# AudioMega_v101.net
KiCad netlist of a schematic drawn in EAGLE
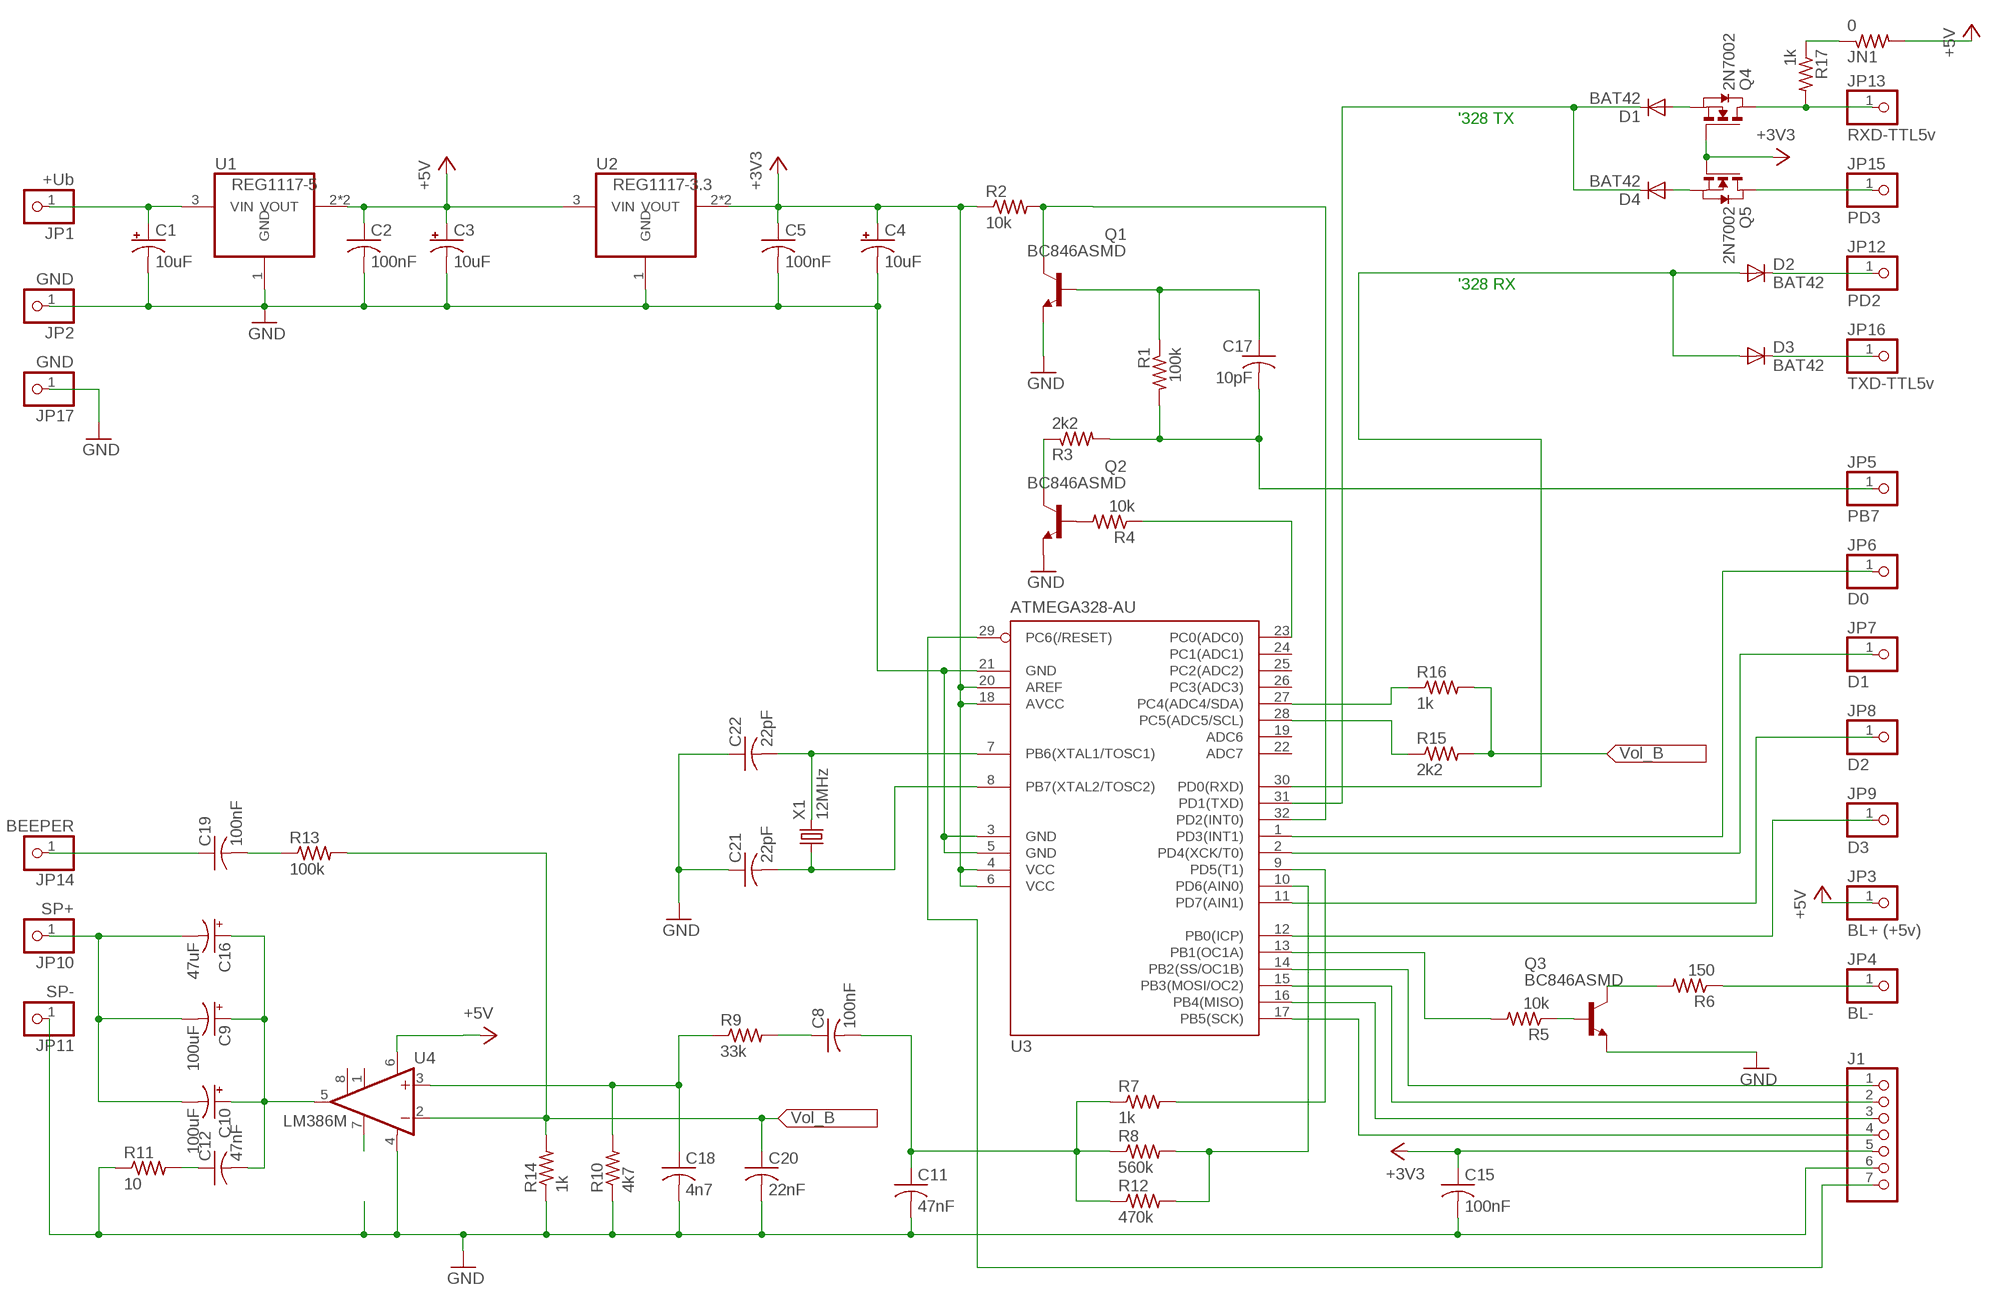
[diagram p0: schematic, sheet 1]

(export (version "E")
  (design (tool "Eeschema 10.0.6"))
  (components
    (comp (ref "C1")
      (value "10uF")
      (footprint "eagle-import:CT3528")
      (libsource (lib "eagle-import") (part "CPOL-USCT3528"))
    )
    (comp (ref "C2")
      (value "100nF")
      (footprint "eagle-import:C1206")
      (libsource (lib "eagle-import") (part "C-USC1206"))
    )
    (comp (ref "C3")
      (value "10uF")
      (footprint "eagle-import:CT3528")
      (libsource (lib "eagle-import") (part "CPOL-USCT3528"))
    )
    (comp (ref "C4")
      (value "10uF")
      (footprint "eagle-import:CT3528")
      (libsource (lib "eagle-import") (part "CPOL-USCT3528"))
    )
    (comp (ref "C5")
      (value "100nF")
      (footprint "eagle-import:C1206")
      (libsource (lib "eagle-import") (part "C-USC1206"))
    )
    (comp (ref "C8")
      (value "100nF")
      (footprint "eagle-import:C1206")
      (libsource (lib "eagle-import") (part "C-USC1206"))
    )
    (comp (ref "C9")
      (value "100uF")
      (footprint "eagle-import:CT6032")
      (libsource (lib "eagle-import") (part "CPOL-USCT6032"))
    )
    (comp (ref "C10")
      (value "100uF")
      (footprint "eagle-import:CT6032")
      (libsource (lib "eagle-import") (part "CPOL-USCT6032"))
    )
    (comp (ref "C11")
      (value "47nF")
      (footprint "eagle-import:C1206")
      (libsource (lib "eagle-import") (part "C-USC1206"))
    )
    (comp (ref "C12")
      (value "47nF")
      (footprint "eagle-import:C1206")
      (libsource (lib "eagle-import") (part "C-USC1206"))
    )
    (comp (ref "C15")
      (value "100nF")
      (footprint "eagle-import:C1206")
      (libsource (lib "eagle-import") (part "C-USC1206"))
    )
    (comp (ref "C16")
      (value "47uF")
      (footprint "eagle-import:CT6032")
      (libsource (lib "eagle-import") (part "CPOL-USCT6032"))
    )
    (comp (ref "C17")
      (value "10pF")
      (footprint "eagle-import:C1206")
      (libsource (lib "eagle-import") (part "C-USC1206"))
    )
    (comp (ref "C18")
      (value "4n7")
      (footprint "eagle-import:C1206")
      (libsource (lib "eagle-import") (part "C-USC1206"))
    )
    (comp (ref "C19")
      (value "100nF")
      (footprint "eagle-import:C1206")
      (libsource (lib "eagle-import") (part "C-USC1206"))
    )
    (comp (ref "C20")
      (value "22nF")
      (footprint "eagle-import:C1206")
      (libsource (lib "eagle-import") (part "C-USC1206"))
    )
    (comp (ref "C21")
      (value "22pF")
      (footprint "eagle-import:C1206")
      (libsource (lib "eagle-import") (part "C-USC1206"))
    )
    (comp (ref "C22")
      (value "22pF")
      (footprint "eagle-import:C1206")
      (libsource (lib "eagle-import") (part "C-USC1206"))
    )
    (comp (ref "D1")
      (value "BAT42")
      (footprint "eagle-import:SOD123")
      (libsource (lib "eagle-import") (part "DIODE-SOD123"))
    )
    (comp (ref "D2")
      (value "BAT42")
      (footprint "eagle-import:SOD123")
      (libsource (lib "eagle-import") (part "DIODE-SOD123"))
    )
    (comp (ref "D3")
      (value "BAT42")
      (footprint "eagle-import:SOD123")
      (libsource (lib "eagle-import") (part "DIODE-SOD123"))
    )
    (comp (ref "D4")
      (value "BAT42")
      (footprint "eagle-import:SOD123")
      (libsource (lib "eagle-import") (part "DIODE-SOD123"))
    )
    (comp (ref "J1")
      (value "PINHD-1X7")
      (footprint "eagle-import:1X07")
      (libsource (lib "eagle-import") (part "PINHD-1X7"))
    )
    (comp (ref "JN1")
      (value "0")
      (footprint "eagle-import:R1206")
      (libsource (lib "eagle-import") (part "R-US_R1206"))
    )
    (comp (ref "JP1")
      (value "+Ub")
      (footprint "eagle-import:1X01")
      (libsource (lib "eagle-import") (part "PINHD-1X1"))
    )
    (comp (ref "JP2")
      (value "GND")
      (footprint "eagle-import:1X01")
      (libsource (lib "eagle-import") (part "PINHD-1X1"))
    )
    (comp (ref "JP3")
      (value "BL+ (+5v)")
      (footprint "eagle-import:1X01")
      (libsource (lib "eagle-import") (part "PINHD-1X1"))
    )
    (comp (ref "JP4")
      (value "BL-")
      (footprint "eagle-import:1X01")
      (libsource (lib "eagle-import") (part "PINHD-1X1"))
    )
    (comp (ref "JP5")
      (value "PB7")
      (footprint "eagle-import:1X01")
      (libsource (lib "eagle-import") (part "PINHD-1X1"))
    )
    (comp (ref "JP6")
      (value "D0")
      (footprint "eagle-import:1X01")
      (libsource (lib "eagle-import") (part "PINHD-1X1"))
    )
    (comp (ref "JP7")
      (value "D1")
      (footprint "eagle-import:1X01")
      (libsource (lib "eagle-import") (part "PINHD-1X1"))
    )
    (comp (ref "JP8")
      (value "D2")
      (footprint "eagle-import:1X01")
      (libsource (lib "eagle-import") (part "PINHD-1X1"))
    )
    (comp (ref "JP9")
      (value "D3")
      (footprint "eagle-import:1X01")
      (libsource (lib "eagle-import") (part "PINHD-1X1"))
    )
    (comp (ref "JP10")
      (value "SP+")
      (footprint "eagle-import:1X01")
      (libsource (lib "eagle-import") (part "PINHD-1X1"))
    )
    (comp (ref "JP11")
      (value "SP-")
      (footprint "eagle-import:1X01")
      (libsource (lib "eagle-import") (part "PINHD-1X1"))
    )
    (comp (ref "JP12")
      (value "PD2")
      (footprint "eagle-import:1X01")
      (libsource (lib "eagle-import") (part "PINHD-1X1"))
    )
    (comp (ref "JP13")
      (value "RXD-TTL5v")
      (footprint "eagle-import:1X01")
      (libsource (lib "eagle-import") (part "PINHD-1X1"))
    )
    (comp (ref "JP14")
      (value "BEEPER")
      (footprint "eagle-import:1X01")
      (libsource (lib "eagle-import") (part "PINHD-1X1"))
    )
    (comp (ref "JP15")
      (value "PD3")
      (footprint "eagle-import:1X01")
      (libsource (lib "eagle-import") (part "PINHD-1X1"))
    )
    (comp (ref "JP16")
      (value "TXD-TTL5v")
      (footprint "eagle-import:1X01")
      (libsource (lib "eagle-import") (part "PINHD-1X1"))
    )
    (comp (ref "JP17")
      (value "GND")
      (footprint "eagle-import:1X01")
      (libsource (lib "eagle-import") (part "PINHD-1X1"))
    )
    (comp (ref "Q1")
      (value "BC846ASMD")
      (footprint "eagle-import:SOT23")
      (libsource (lib "eagle-import") (part "BC846SMDA"))
    )
    (comp (ref "Q2")
      (value "BC846ASMD")
      (footprint "eagle-import:SOT23")
      (libsource (lib "eagle-import") (part "BC846SMDA"))
    )
    (comp (ref "Q3")
      (value "BC846ASMD")
      (footprint "eagle-import:SOT23")
      (libsource (lib "eagle-import") (part "BC846SMDA"))
    )
    (comp (ref "Q4")
      (value "2N7002")
      (footprint "eagle-import:SOT-23")
      (libsource (lib "eagle-import") (part "NMOSSOT23"))
    )
    (comp (ref "Q5")
      (value "2N7002")
      (footprint "eagle-import:SOT-23")
      (fields (field (name "OC_FARNELL") "unknown") (field (name "OC_NEWARK") "unknown"))
      (libsource (lib "eagle-import") (part "NMOSSOT23"))
    )
    (comp (ref "R1")
      (value "100k")
      (footprint "eagle-import:R1206")
      (libsource (lib "eagle-import") (part "R-US_R1206"))
    )
    (comp (ref "R2")
      (value "10k")
      (footprint "eagle-import:R1206")
      (libsource (lib "eagle-import") (part "R-US_R1206"))
    )
    (comp (ref "R3")
      (value "2k2")
      (footprint "eagle-import:R1206")
      (libsource (lib "eagle-import") (part "R-US_R1206"))
    )
    (comp (ref "R4")
      (value "10k")
      (footprint "eagle-import:R1206")
      (libsource (lib "eagle-import") (part "R-US_R1206"))
    )
    (comp (ref "R5")
      (value "10k")
      (footprint "eagle-import:R1206")
      (libsource (lib "eagle-import") (part "R-US_R1206"))
    )
    (comp (ref "R6")
      (value "150")
      (footprint "eagle-import:R1206")
      (libsource (lib "eagle-import") (part "R-US_R1206"))
    )
    (comp (ref "R7")
      (value "1k")
      (footprint "eagle-import:R1206")
      (libsource (lib "eagle-import") (part "R-US_R1206"))
    )
    (comp (ref "R8")
      (value "560k")
      (footprint "eagle-import:R1206")
      (libsource (lib "eagle-import") (part "R-US_R1206"))
    )
    (comp (ref "R9")
      (value "33k")
      (footprint "eagle-import:R1206")
      (libsource (lib "eagle-import") (part "R-US_R1206"))
    )
    (comp (ref "R10")
      (value "4k7")
      (footprint "eagle-import:R1206")
      (libsource (lib "eagle-import") (part "R-US_R1206"))
    )
    (comp (ref "R11")
      (value "10")
      (footprint "eagle-import:R1206")
      (libsource (lib "eagle-import") (part "R-US_R1206"))
    )
    (comp (ref "R12")
      (value "470k")
      (footprint "eagle-import:R1206")
      (libsource (lib "eagle-import") (part "R-US_R1206"))
    )
    (comp (ref "R13")
      (value "100k")
      (footprint "eagle-import:R1206")
      (libsource (lib "eagle-import") (part "R-US_R1206"))
    )
    (comp (ref "R14")
      (value "1k")
      (footprint "eagle-import:R1206")
      (libsource (lib "eagle-import") (part "R-US_R1206"))
    )
    (comp (ref "R15")
      (value "2k2")
      (footprint "eagle-import:R1206")
      (libsource (lib "eagle-import") (part "R-US_R1206"))
    )
    (comp (ref "R16")
      (value "1k")
      (footprint "eagle-import:R1206")
      (libsource (lib "eagle-import") (part "R-US_R1206"))
    )
    (comp (ref "R17")
      (value "1k")
      (footprint "eagle-import:R1206")
      (libsource (lib "eagle-import") (part "R-US_R1206"))
    )
    (comp (ref "U1")
      (value "REG1117-5")
      (footprint "eagle-import:SOT223")
      (fields (field (name "MPN") "REG1117"))
      (libsource (lib "eagle-import") (part "REG1117"))
    )
    (comp (ref "U2")
      (value "REG1117-3.3")
      (footprint "eagle-import:SOT223")
      (fields (field (name "MPN") "REG1117"))
      (libsource (lib "eagle-import") (part "REG1117"))
    )
    (comp (ref "U3")
      (value "ATMEGA328-AU")
      (footprint "eagle-import:TQFP32-08")
      (fields (field (name "MPN") "ATMEGA8-16AU"))
      (libsource (lib "eagle-import") (part "MEGA8-AI"))
    )
    (comp (ref "U4")
      (value "LM386M")
      (footprint "eagle-import:SO08")
      (libsource (lib "eagle-import") (part "LM386?-M1"))
    )
    (comp (ref "X1")
      (value "12MHz")
      (footprint "eagle-import:HC49UP")
      (libsource (lib "eagle-import") (part "CRYSTALHC49UP"))
    )
  )
  (nets
    (net (code "1") (name "+3V3") (class "Default")
      (node (ref "C15") (pin "1") (pinfunction "1_1") (pintype "passive"))
      (node (ref "C4") (pin "+") (pinfunction "+_+") (pintype "passive"))
      (node (ref "C5") (pin "1") (pinfunction "1_1") (pintype "passive"))
      (node (ref "J1") (pin "5") (pinfunction "5_5") (pintype "passive"))
      (node (ref "Q4") (pin "3") (pinfunction "G_3") (pintype "passive"))
      (node (ref "Q5") (pin "3") (pinfunction "G_3") (pintype "passive"))
      (node (ref "R2") (pin "1") (pinfunction "1_1") (pintype "passive"))
      (node (ref "U2") (pin "2") (pinfunction "VOUT_2") (pintype "output"))
      (node (ref "U2") (pin "4") (pinfunction "VOUT_4") (pintype "output"))
      (node (ref "U3") (pin "18") (pinfunction "AVCC_18") (pintype "power_in"))
      (node (ref "U3") (pin "20") (pinfunction "AREF_20") (pintype "passive"))
      (node (ref "U3") (pin "4") (pinfunction "VCC_4") (pintype "power_in"))
      (node (ref "U3") (pin "6") (pinfunction "VCC_6") (pintype "power_in"))
    )
    (net (code "2") (name "+5V") (class "Default")
      (node (ref "C2") (pin "1") (pinfunction "1_1") (pintype "passive"))
      (node (ref "C3") (pin "+") (pinfunction "+_+") (pintype "passive"))
      (node (ref "JN1") (pin "2") (pinfunction "2_2") (pintype "passive"))
      (node (ref "JP3") (pin "1") (pinfunction "1_1") (pintype "passive"))
      (node (ref "U1") (pin "2") (pinfunction "VOUT_2") (pintype "output"))
      (node (ref "U1") (pin "4") (pinfunction "VOUT_4") (pintype "output"))
      (node (ref "U2") (pin "3") (pinfunction "VIN_3") (pintype "input"))
      (node (ref "U4") (pin "6") (pinfunction "VS_6") (pintype "power_in"))
    )
    (net (code "3") (name "/VOL_B") (class "Default")
      (node (ref "C20") (pin "1") (pinfunction "1_1") (pintype "passive"))
      (node (ref "R13") (pin "2") (pinfunction "2_2") (pintype "passive"))
      (node (ref "R14") (pin "2") (pinfunction "2_2") (pintype "passive"))
      (node (ref "R15") (pin "2") (pinfunction "2_2") (pintype "passive"))
      (node (ref "R16") (pin "2") (pinfunction "2_2") (pintype "passive"))
      (node (ref "U4") (pin "2") (pinfunction "-IN_2") (pintype "input"))
    )
    (net (code "4") (name "GND") (class "Default")
      (node (ref "C1") (pin "-") (pinfunction "-_-") (pintype "passive"))
      (node (ref "C11") (pin "2") (pinfunction "2_2") (pintype "passive"))
      (node (ref "C15") (pin "2") (pinfunction "2_2") (pintype "passive"))
      (node (ref "C18") (pin "2") (pinfunction "2_2") (pintype "passive"))
      (node (ref "C2") (pin "2") (pinfunction "2_2") (pintype "passive"))
      (node (ref "C20") (pin "2") (pinfunction "2_2") (pintype "passive"))
      (node (ref "C21") (pin "1") (pinfunction "1_1") (pintype "passive"))
      (node (ref "C22") (pin "1") (pinfunction "1_1") (pintype "passive"))
      (node (ref "C3") (pin "-") (pinfunction "-_-") (pintype "passive"))
      (node (ref "C4") (pin "-") (pinfunction "-_-") (pintype "passive"))
      (node (ref "C5") (pin "2") (pinfunction "2_2") (pintype "passive"))
      (node (ref "J1") (pin "6") (pinfunction "6_6") (pintype "passive"))
      (node (ref "JP11") (pin "1") (pinfunction "1_1") (pintype "passive"))
      (node (ref "JP17") (pin "1") (pinfunction "1_1") (pintype "passive"))
      (node (ref "JP2") (pin "1") (pinfunction "1_1") (pintype "passive"))
      (node (ref "Q1") (pin "2") (pinfunction "E_2") (pintype "passive"))
      (node (ref "Q2") (pin "2") (pinfunction "E_2") (pintype "passive"))
      (node (ref "Q3") (pin "2") (pinfunction "E_2") (pintype "passive"))
      (node (ref "R10") (pin "1") (pinfunction "1_1") (pintype "passive"))
      (node (ref "R11") (pin "1") (pinfunction "1_1") (pintype "passive"))
      (node (ref "R14") (pin "1") (pinfunction "1_1") (pintype "passive"))
      (node (ref "U1") (pin "1") (pinfunction "GND_1") (pintype "power_in"))
      (node (ref "U2") (pin "1") (pinfunction "GND_1") (pintype "power_in"))
      (node (ref "U3") (pin "21") (pinfunction "GND_21") (pintype "power_in"))
      (node (ref "U3") (pin "3") (pinfunction "GND_3") (pintype "power_in"))
      (node (ref "U3") (pin "5") (pinfunction "GND_5") (pintype "power_in"))
      (node (ref "U4") (pin "4") (pinfunction "GND_4") (pintype "power_in"))
    )
    (net (code "5") (name "Net-(C8-Pad1)") (class "Default")
      (node (ref "C8") (pin "1") (pinfunction "1_1") (pintype "passive"))
      (node (ref "R9") (pin "2") (pinfunction "2_2") (pintype "passive"))
    )
    (net (code "6") (name "Net-(C10-Pad-)") (class "Default")
      (node (ref "C10") (pin "-") (pinfunction "-_-") (pintype "passive"))
      (node (ref "C16") (pin "-") (pinfunction "-_-") (pintype "passive"))
      (node (ref "C9") (pin "-") (pinfunction "-_-") (pintype "passive"))
      (node (ref "JP10") (pin "1") (pinfunction "1_1") (pintype "passive"))
    )
    (net (code "7") (name "Net-(C11-Pad1)") (class "Default")
      (node (ref "C11") (pin "1") (pinfunction "1_1") (pintype "passive"))
      (node (ref "C8") (pin "2") (pinfunction "2_2") (pintype "passive"))
      (node (ref "R12") (pin "1") (pinfunction "1_1") (pintype "passive"))
      (node (ref "R7") (pin "1") (pinfunction "1_1") (pintype "passive"))
      (node (ref "R8") (pin "1") (pinfunction "1_1") (pintype "passive"))
    )
    (net (code "8") (name "Net-(C12-Pad1)") (class "Default")
      (node (ref "C12") (pin "1") (pinfunction "1_1") (pintype "passive"))
      (node (ref "R11") (pin "2") (pinfunction "2_2") (pintype "passive"))
    )
    (net (code "9") (name "Net-(C17-Pad2)") (class "Default")
      (node (ref "C17") (pin "2") (pinfunction "2_2") (pintype "passive"))
      (node (ref "JP5") (pin "1") (pinfunction "1_1") (pintype "passive"))
      (node (ref "R1") (pin "2") (pinfunction "2_2") (pintype "passive"))
      (node (ref "R3") (pin "2") (pinfunction "2_2") (pintype "passive"))
    )
    (net (code "10") (name "Net-(C19-Pad1)") (class "Default")
      (node (ref "C19") (pin "1") (pinfunction "1_1") (pintype "passive"))
      (node (ref "JP14") (pin "1") (pinfunction "1_1") (pintype "passive"))
    )
    (net (code "11") (name "Net-(C19-Pad2)") (class "Default")
      (node (ref "C19") (pin "2") (pinfunction "2_2") (pintype "passive"))
      (node (ref "R13") (pin "1") (pinfunction "1_1") (pintype "passive"))
    )
    (net (code "12") (name "Net-(D2-PadC)") (class "Default")
      (node (ref "D2") (pin "C") (pinfunction "C_C") (pintype "passive"))
      (node (ref "JP12") (pin "1") (pinfunction "1_1") (pintype "passive"))
    )
    (net (code "13") (name "Net-(D3-PadC)") (class "Default")
      (node (ref "D3") (pin "C") (pinfunction "C_C") (pintype "passive"))
      (node (ref "JP16") (pin "1") (pinfunction "1_1") (pintype "passive"))
    )
    (net (code "14") (name "Net-(JN1-Pad1)") (class "Default")
      (node (ref "JN1") (pin "1") (pinfunction "1_1") (pintype "passive"))
      (node (ref "R17") (pin "1") (pinfunction "1_1") (pintype "passive"))
    )
    (net (code "15") (name "Net-(JP4-Pad1)") (class "Default")
      (node (ref "JP4") (pin "1") (pinfunction "1_1") (pintype "passive"))
      (node (ref "R6") (pin "1") (pinfunction "1_1") (pintype "passive"))
    )
    (net (code "16") (name "Net-(Q1-B)") (class "Default")
      (node (ref "C17") (pin "1") (pinfunction "1_1") (pintype "passive"))
      (node (ref "Q1") (pin "1") (pinfunction "B_1") (pintype "passive"))
      (node (ref "R1") (pin "1") (pinfunction "1_1") (pintype "passive"))
    )
    (net (code "17") (name "Net-(Q1-C)") (class "Default")
      (node (ref "Q1") (pin "3") (pinfunction "C_3") (pintype "passive"))
      (node (ref "R2") (pin "2") (pinfunction "2_2") (pintype "passive"))
      (node (ref "U3") (pin "32") (pinfunction "PD2(INT0)_32") (pintype "bidirectional"))
    )
    (net (code "18") (name "Net-(Q2-B)") (class "Default")
      (node (ref "Q2") (pin "1") (pinfunction "B_1") (pintype "passive"))
      (node (ref "R4") (pin "2") (pinfunction "2_2") (pintype "passive"))
    )
    (net (code "19") (name "Net-(Q2-C)") (class "Default")
      (node (ref "Q2") (pin "3") (pinfunction "C_3") (pintype "passive"))
      (node (ref "R3") (pin "1") (pinfunction "1_1") (pintype "passive"))
    )
    (net (code "20") (name "Net-(Q3-B)") (class "Default")
      (node (ref "Q3") (pin "1") (pinfunction "B_1") (pintype "passive"))
      (node (ref "R5") (pin "1") (pinfunction "1_1") (pintype "passive"))
    )
    (net (code "21") (name "Net-(Q3-C)") (class "Default")
      (node (ref "Q3") (pin "3") (pinfunction "C_3") (pintype "passive"))
      (node (ref "R6") (pin "2") (pinfunction "2_2") (pintype "passive"))
    )
    (net (code "22") (name "Net-(Q4-D)") (class "Default")
      (node (ref "JP13") (pin "1") (pinfunction "1_1") (pintype "passive"))
      (node (ref "Q4") (pin "1") (pinfunction "D_1") (pintype "passive"))
      (node (ref "R17") (pin "2") (pinfunction "2_2") (pintype "passive"))
    )
    (net (code "23") (name "Net-(Q4-S)") (class "Default")
      (node (ref "D1") (pin "A") (pinfunction "A_A") (pintype "passive"))
      (node (ref "Q4") (pin "2") (pinfunction "S_2") (pintype "passive"))
    )
    (net (code "24") (name "Net-(Q5-D)") (class "Default")
      (node (ref "JP15") (pin "1") (pinfunction "1_1") (pintype "passive"))
      (node (ref "Q5") (pin "1") (pinfunction "D_1") (pintype "passive"))
    )
    (net (code "25") (name "Net-(Q5-S)") (class "Default")
      (node (ref "D4") (pin "A") (pinfunction "A_A") (pintype "passive"))
      (node (ref "Q5") (pin "2") (pinfunction "S_2") (pintype "passive"))
    )
    (net (code "26") (name "Net-(U1-VIN)") (class "Default")
      (node (ref "C1") (pin "+") (pinfunction "+_+") (pintype "passive"))
      (node (ref "JP1") (pin "1") (pinfunction "1_1") (pintype "passive"))
      (node (ref "U1") (pin "3") (pinfunction "VIN_3") (pintype "input"))
    )
    (net (code "27") (name "Net-(U3-PB0(ICP))") (class "Default")
      (node (ref "JP9") (pin "1") (pinfunction "1_1") (pintype "passive"))
      (node (ref "U3") (pin "12") (pinfunction "PB0(ICP)_12") (pintype "bidirectional"))
    )
    (net (code "28") (name "Net-(U3-PB1(OC1A))") (class "Default")
      (node (ref "R5") (pin "2") (pinfunction "2_2") (pintype "passive"))
      (node (ref "U3") (pin "13") (pinfunction "PB1(OC1A)_13") (pintype "bidirectional"))
    )
    (net (code "29") (name "Net-(U3-PB2(SS{slash}OC1B))") (class "Default")
      (node (ref "J1") (pin "1") (pinfunction "1_1") (pintype "passive"))
      (node (ref "U3") (pin "14") (pinfunction "PB2(SS/OC1B)_14") (pintype "bidirectional"))
    )
    (net (code "30") (name "Net-(U3-PB3(MOSI{slash}OC2))") (class "Default")
      (node (ref "J1") (pin "2") (pinfunction "2_2") (pintype "passive"))
      (node (ref "U3") (pin "15") (pinfunction "PB3(MOSI/OC2)_15") (pintype "bidirectional"))
    )
    (net (code "31") (name "Net-(U3-PB4(MISO))") (class "Default")
      (node (ref "J1") (pin "3") (pinfunction "3_3") (pintype "passive"))
      (node (ref "U3") (pin "16") (pinfunction "PB4(MISO)_16") (pintype "bidirectional"))
    )
    (net (code "32") (name "Net-(U3-PB5(SCK))") (class "Default")
      (node (ref "J1") (pin "4") (pinfunction "4_4") (pintype "passive"))
      (node (ref "U3") (pin "17") (pinfunction "PB5(SCK)_17") (pintype "bidirectional"))
    )
    (net (code "33") (name "Net-(U3-PB6(XTAL1{slash}TOSC1))") (class "Default")
      (node (ref "C22") (pin "2") (pinfunction "2_2") (pintype "passive"))
      (node (ref "U3") (pin "7") (pinfunction "PB6(XTAL1/TOSC1)_7") (pintype "bidirectional"))
      (node (ref "X1") (pin "2") (pinfunction "2_2") (pintype "passive"))
    )
    (net (code "34") (name "Net-(U3-PB7(XTAL2{slash}TOSC2))") (class "Default")
      (node (ref "C21") (pin "2") (pinfunction "2_2") (pintype "passive"))
      (node (ref "U3") (pin "8") (pinfunction "PB7(XTAL2/TOSC2)_8") (pintype "bidirectional"))
      (node (ref "X1") (pin "1") (pinfunction "1_1") (pintype "passive"))
    )
    (net (code "35") (name "Net-(U3-PC0(ADC0))") (class "Default")
      (node (ref "R4") (pin "1") (pinfunction "1_1") (pintype "passive"))
      (node (ref "U3") (pin "23") (pinfunction "PC0(ADC0)_23") (pintype "bidirectional"))
    )
    (net (code "36") (name "Net-(U3-PC4(ADC4{slash}SDA))") (class "Default")
      (node (ref "R16") (pin "1") (pinfunction "1_1") (pintype "passive"))
      (node (ref "U3") (pin "27") (pinfunction "PC4(ADC4/SDA)_27") (pintype "bidirectional"))
    )
    (net (code "37") (name "Net-(U3-PC5(ADC5{slash}SCL))") (class "Default")
      (node (ref "R15") (pin "1") (pinfunction "1_1") (pintype "passive"))
      (node (ref "U3") (pin "28") (pinfunction "PC5(ADC5/SCL)_28") (pintype "bidirectional"))
    )
    (net (code "38") (name "Net-(U3-PC6({slash}RESET))") (class "Default")
      (node (ref "J1") (pin "7") (pinfunction "7_7") (pintype "passive"))
      (node (ref "U3") (pin "29") (pinfunction "PC6(/RESET)_29") (pintype "bidirectional"))
    )
    (net (code "39") (name "Net-(U3-PD0(RXD))") (class "Default")
      (node (ref "D2") (pin "A") (pinfunction "A_A") (pintype "passive"))
      (node (ref "D3") (pin "A") (pinfunction "A_A") (pintype "passive"))
      (node (ref "U3") (pin "30") (pinfunction "PD0(RXD)_30") (pintype "bidirectional"))
    )
    (net (code "40") (name "Net-(U3-PD1(TXD))") (class "Default")
      (node (ref "D1") (pin "C") (pinfunction "C_C") (pintype "passive"))
      (node (ref "D4") (pin "C") (pinfunction "C_C") (pintype "passive"))
      (node (ref "U3") (pin "31") (pinfunction "PD1(TXD)_31") (pintype "bidirectional"))
    )
    (net (code "41") (name "Net-(U3-PD3(INT1))") (class "Default")
      (node (ref "JP6") (pin "1") (pinfunction "1_1") (pintype "passive"))
      (node (ref "U3") (pin "1") (pinfunction "PD3(INT1)_1") (pintype "bidirectional"))
    )
    (net (code "42") (name "Net-(U3-PD4(XCK{slash}T0))") (class "Default")
      (node (ref "JP7") (pin "1") (pinfunction "1_1") (pintype "passive"))
      (node (ref "U3") (pin "2") (pinfunction "PD4(XCK/T0)_2") (pintype "bidirectional"))
    )
    (net (code "43") (name "Net-(U3-PD5(T1))") (class "Default")
      (node (ref "R7") (pin "2") (pinfunction "2_2") (pintype "passive"))
      (node (ref "U3") (pin "9") (pinfunction "PD5(T1)_9") (pintype "bidirectional"))
    )
    (net (code "44") (name "Net-(U3-PD6(AIN0))") (class "Default")
      (node (ref "R12") (pin "2") (pinfunction "2_2") (pintype "passive"))
      (node (ref "R8") (pin "2") (pinfunction "2_2") (pintype "passive"))
      (node (ref "U3") (pin "10") (pinfunction "PD6(AIN0)_10") (pintype "bidirectional"))
    )
    (net (code "45") (name "Net-(U3-PD7(AIN1))") (class "Default")
      (node (ref "JP8") (pin "1") (pinfunction "1_1") (pintype "passive"))
      (node (ref "U3") (pin "11") (pinfunction "PD7(AIN1)_11") (pintype "bidirectional"))
    )
    (net (code "46") (name "Net-(U4-+IN)") (class "Default")
      (node (ref "C18") (pin "1") (pinfunction "1_1") (pintype "passive"))
      (node (ref "R10") (pin "2") (pinfunction "2_2") (pintype "passive"))
      (node (ref "R9") (pin "1") (pinfunction "1_1") (pintype "passive"))
      (node (ref "U4") (pin "3") (pinfunction "+IN_3") (pintype "input"))
    )
    (net (code "47") (name "Net-(U4-OUT)") (class "Default")
      (node (ref "C10") (pin "+") (pinfunction "+_+") (pintype "passive"))
      (node (ref "C12") (pin "2") (pinfunction "2_2") (pintype "passive"))
      (node (ref "C16") (pin "+") (pinfunction "+_+") (pintype "passive"))
      (node (ref "C9") (pin "+") (pinfunction "+_+") (pintype "passive"))
      (node (ref "U4") (pin "5") (pinfunction "OUT_5") (pintype "output"))
    )
    (net (code "48") (name "unconnected-(U3-ADC6-Pad19)") (class "Default")
      (node (ref "U3") (pin "19") (pinfunction "ADC6_19") (pintype "bidirectional"))
    )
    (net (code "49") (name "unconnected-(U3-ADC7-Pad22)") (class "Default")
      (node (ref "U3") (pin "22") (pinfunction "ADC7_22") (pintype "bidirectional"))
    )
    (net (code "50") (name "unconnected-(U3-PC1(ADC1)-Pad24)") (class "Default")
      (node (ref "U3") (pin "24") (pinfunction "PC1(ADC1)_24") (pintype "bidirectional"))
    )
    (net (code "51") (name "unconnected-(U3-PC2(ADC2)-Pad25)") (class "Default")
      (node (ref "U3") (pin "25") (pinfunction "PC2(ADC2)_25") (pintype "bidirectional"))
    )
    (net (code "52") (name "unconnected-(U3-PC3(ADC3)-Pad26)") (class "Default")
      (node (ref "U3") (pin "26") (pinfunction "PC3(ADC3)_26") (pintype "bidirectional"))
    )
    (net (code "53") (name "unconnected-(U4-BYPASS-Pad7)") (class "Default")
      (node (ref "U4") (pin "7") (pinfunction "BYPASS_7") (pintype "passive"))
    )
    (net (code "54") (name "unconnected-(U4-GAIN-Pad1)") (class "Default")
      (node (ref "U4") (pin "1") (pinfunction "GAIN_1") (pintype "passive"))
    )
    (net (code "55") (name "unconnected-(U4-GAIN-Pad8)") (class "Default")
      (node (ref "U4") (pin "8") (pinfunction "GAIN_8") (pintype "passive"))
    )
  )
)
